# SCH_blaster_2025-10-02.net
KiCad netlist of a schematic drawn in EasyEDA
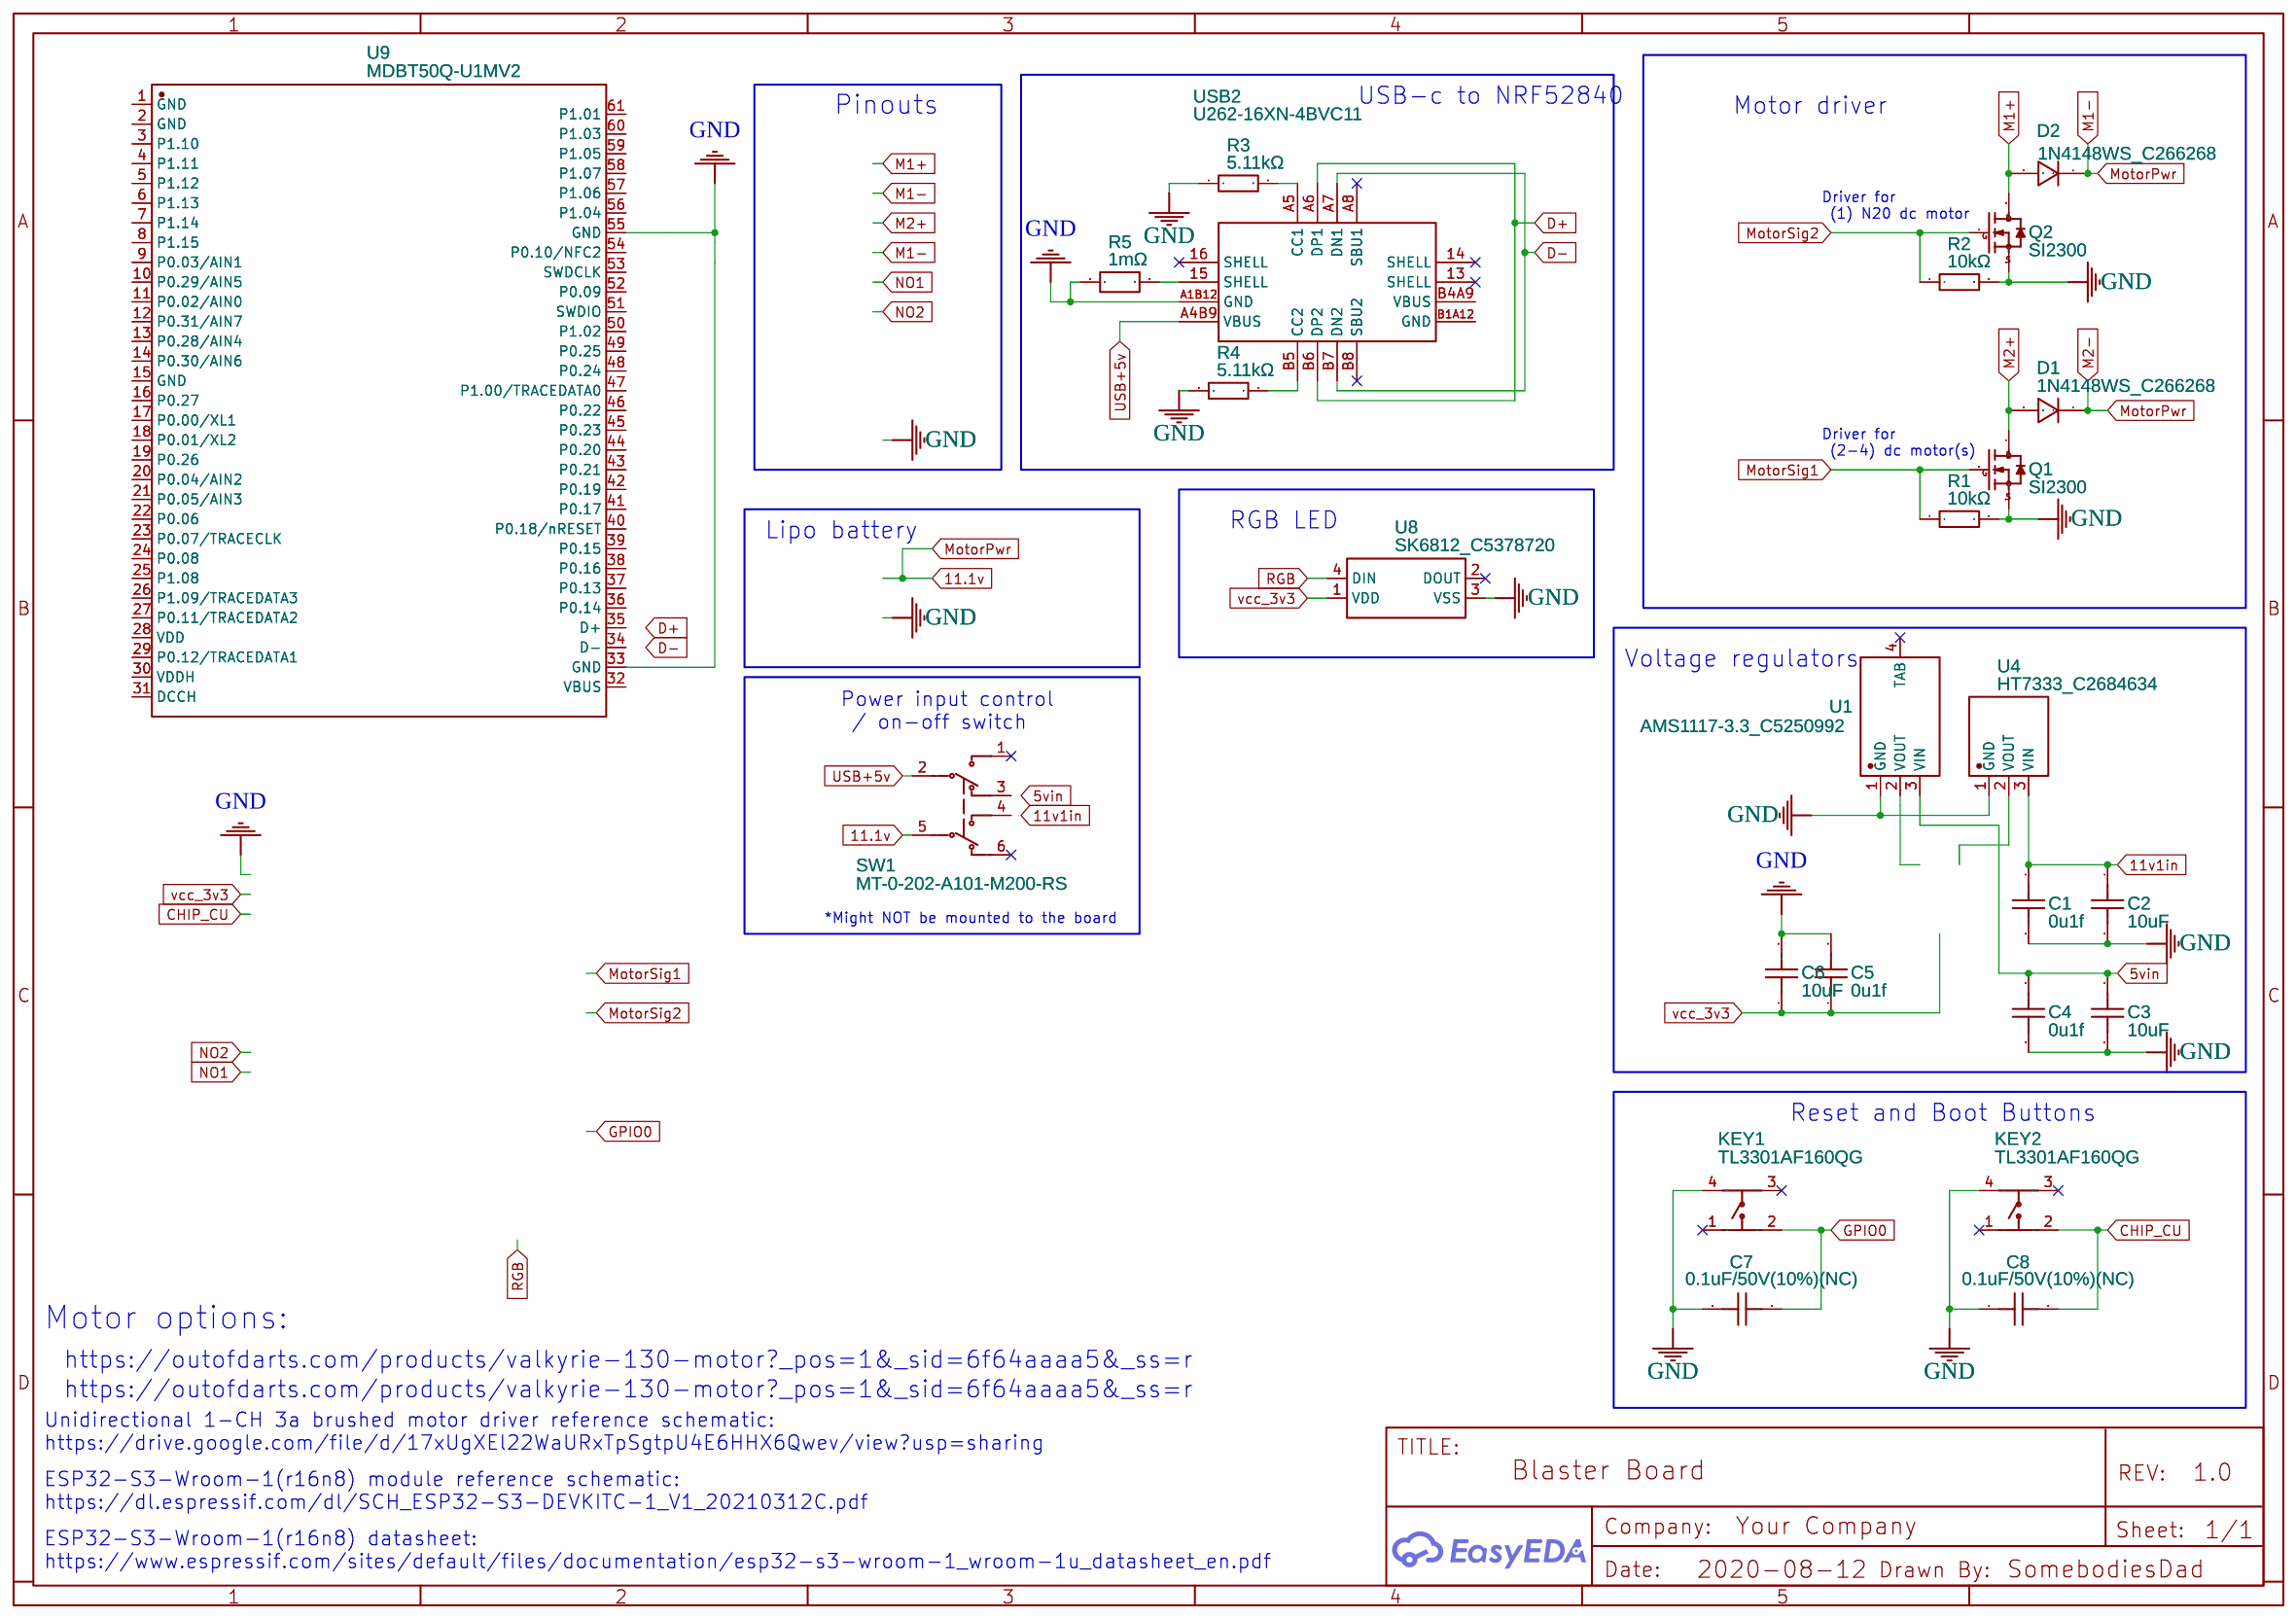
[diagram p0: Blaster Board]
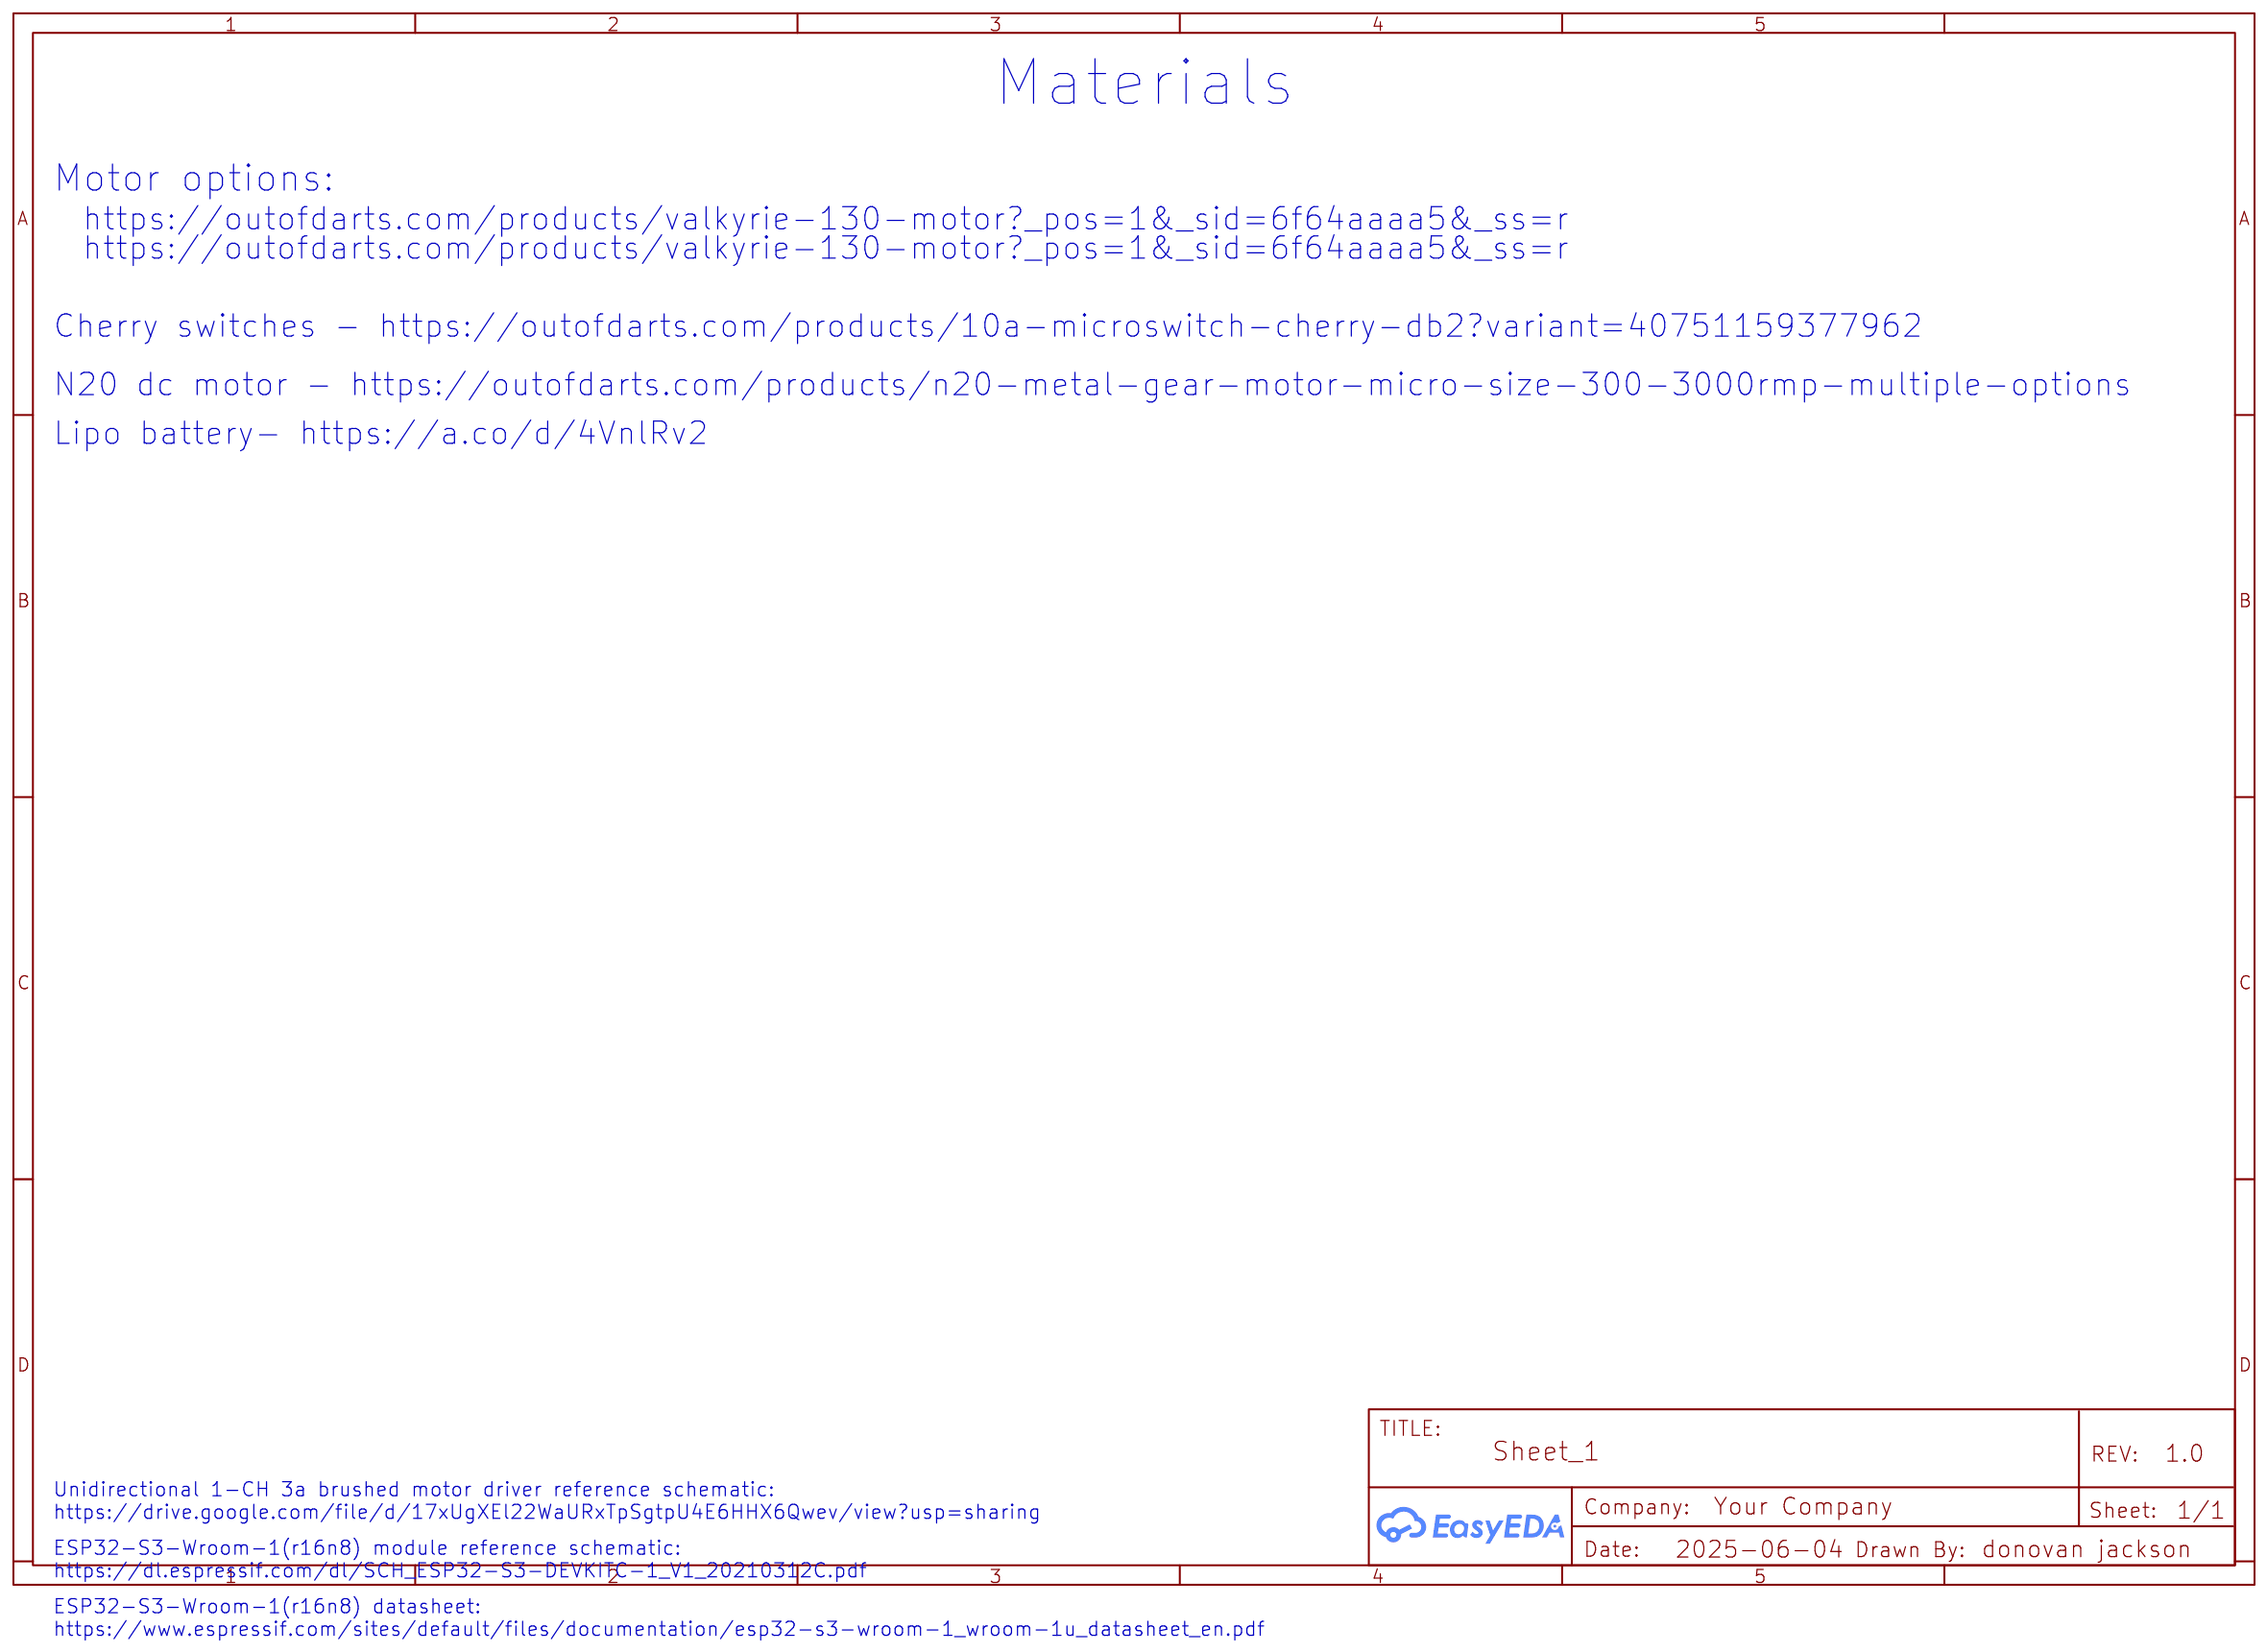
[diagram p1: Materials]

(export (version "E")
  (design (tool "Eeschema 10.0.6"))
  (components
    (comp (ref "C1") (value "0u1f") (libsource (lib "") (part "C_0603_US")))
    (comp (ref "C2") (value "10uF") (libsource (lib "") (part "C_0603_US")))
    (comp (ref "C3") (value "10uF") (libsource (lib "") (part "C_0603_US")))
    (comp (ref "C4") (value "0u1f") (libsource (lib "") (part "C_0603_US")))
    (comp (ref "C5") (value "0u1f") (libsource (lib "") (part "C_0603_US_1")))
    (comp (ref "C6") (value "10uF") (libsource (lib "") (part "C_0603_US_1")))
    (comp (ref "C7") (value "0.1uF/50V(10%)(NC)") (libsource (lib "") (part "C_0603_US_2")))
    (comp (ref "C8") (value "0.1uF/50V(10%)(NC)") (libsource (lib "") (part "C_0603_US_2")))
    (comp (ref "D1")
      (value "1N4148WS_C266268")
      (fields (field (name "Manufacturer Part") "1N4148WS") (field (name "Manufacturer") "GOOD-ARK(固锝)"))
      (libsource (lib "") (part "1N4148WS_C266268"))
    )
    (comp (ref "D2")
      (value "1N4148WS_C266268")
      (fields (field (name "Manufacturer Part") "1N4148WS") (field (name "Manufacturer") "GOOD-ARK(固锝)"))
      (libsource (lib "") (part "1N4148WS_C266268"))
    )
    (comp (ref "KEY1")
      (value "TL3301AF160QG")
      (fields (field (name "Manufacturer") "E-Switch"))
      (libsource (lib "") (part "TL3301AF160QG"))
    )
    (comp (ref "KEY2")
      (value "TL3301AF160QG")
      (fields (field (name "Manufacturer") "E-Switch"))
      (libsource (lib "") (part "TL3301AF160QG"))
    )
    (comp (ref "Q1")
      (value "SI2300")
      (fields (field (name "Manufacturer") "Hottech(合科泰)"))
      (libsource (lib "") (part "SI2300"))
    )
    (comp (ref "Q2")
      (value "SI2300")
      (fields (field (name "Manufacturer") "Hottech(合科泰)"))
      (libsource (lib "") (part "SI2300"))
    )
    (comp (ref "R1")
      (value "10kΩ")
      (fields
        (field (name "Manufacturer Part") "0805W8F1002T5E")
        (field (name "Manufacturer") "UNI-ROYAL(厚声)")
      )
      (libsource (lib "") (part "0805W8F1002T5E"))
    )
    (comp (ref "R2")
      (value "10kΩ")
      (fields
        (field (name "Manufacturer Part") "0805W8F1002T5E")
        (field (name "Manufacturer") "UNI-ROYAL(厚声)")
      )
      (libsource (lib "") (part "0805W8F1002T5E"))
    )
    (comp (ref "R3")
      (value "5.11kΩ")
      (fields
        (field (name "Manufacturer Part") "0201WMF5111TEE")
        (field (name "Manufacturer") "UNI-ROYAL(厚声)")
      )
      (libsource (lib "") (part "0201WMF5111TEE"))
    )
    (comp (ref "R4")
      (value "5.11kΩ")
      (fields
        (field (name "Manufacturer Part") "0201WMF5111TEE")
        (field (name "Manufacturer") "UNI-ROYAL(厚声)")
      )
      (libsource (lib "") (part "0201WMF5111TEE"))
    )
    (comp (ref "R5")
      (value "1mΩ")
      (fields
        (field (name "Manufacturer Part") "WFC08051L000FE66")
        (field (name "Manufacturer") "VISHAY(威世)")
      )
      (libsource (lib "") (part "WFC08051L000FE66"))
    )
    (comp (ref "SW1")
      (value "MT-0-202-A101-M200-RS")
      (fields (field (name "Manufacturer") "YUEN FUNG(源丰)"))
      (libsource (lib "") (part "MT-0-202-A101-M200-RS"))
    )
    (comp (ref "U1")
      (value "AMS1117-3.3_C5250992")
      (fields (field (name "Manufacturer Part") "AMS1117-3.3") (field (name "Manufacturer") "TWGMC(台湾迪嘉)"))
      (libsource (lib "") (part "AMS1117-3.3_C5250992"))
    )
    (comp (ref "U4")
      (value "HT7333_C2684634")
      (fields (field (name "Manufacturer Part") "HT7333") (field (name "Manufacturer") "国芯佳品"))
      (libsource (lib "") (part "HT7333_C2684634"))
    )
    (comp (ref "U8")
      (value "SK6812_C5378720")
      (fields (field (name "Manufacturer Part") "SK6812") (field (name "Manufacturer") "欧思科光电"))
      (libsource (lib "") (part "SK6812_C5378720"))
    )
    (comp (ref "U9")
      (value "MDBT50Q-U1MV2")
      (fields (field (name "Manufacturer") "RAYTAC"))
      (libsource (lib "") (part "MDBT50Q-U1MV2"))
    )
    (comp (ref "USB2")
      (value "U262-16XN-4BVC11")
      (fields
        (field (name "Manufacturer Part") "U262-161N-4BVC11")
        (field (name "Manufacturer") "XKB Connection(中国星坤)")
      )
      (libsource (lib "") (part "U262-16XN-4BVC11"))
    )
  )
  (nets
    (net (code "1") (name "5vin") (class "Default")
      (node (ref "C3") (pin "1") (pinfunction "1_1") (pintype "unspecified"))
      (node (ref "C4") (pin "1") (pinfunction "1_1") (pintype "unspecified"))
      (node (ref "U1") (pin "3") (pinfunction "VIN_3") (pintype "unspecified"))
    )
    (net (code "2") (name "11.1v") (class "Default")
      (node (ref "D1") (pin "1") (pinfunction "1_1") (pintype "unspecified"))
      (node (ref "D2") (pin "1") (pinfunction "1_1") (pintype "unspecified"))
      (node (ref "SW1") (pin "5") (pinfunction "5_5") (pintype "unspecified"))
    )
    (net (code "3") (name "11v1in") (class "Default")
      (node (ref "C1") (pin "1") (pinfunction "1_1") (pintype "unspecified"))
      (node (ref "C2") (pin "1") (pinfunction "1_1") (pintype "unspecified"))
      (node (ref "U4") (pin "3") (pinfunction "VIN_3") (pintype "unspecified"))
    )
    (net (code "4") (name "CHIP_CU") (class "Default")
      (node (ref "C8") (pin "2") (pinfunction "2_2") (pintype "unspecified"))
      (node (ref "KEY2") (pin "2") (pinfunction "2_2") (pintype "unspecified"))
    )
    (net (code "5") (name "D+") (class "Default")
      (node (ref "USB2") (pin "A6") (pinfunction "DP1_A6") (pintype "unspecified"))
      (node (ref "USB2") (pin "B6") (pinfunction "DP2_B6") (pintype "unspecified"))
    )
    (net (code "6") (name "D-") (class "Default")
      (node (ref "USB2") (pin "A7") (pinfunction "DN1_A7") (pintype "unspecified"))
      (node (ref "USB2") (pin "B7") (pinfunction "DN2_B7") (pintype "unspecified"))
    )
    (net (code "7") (name "GND") (class "Default")
      (node (ref "C1") (pin "2") (pinfunction "2_2") (pintype "unspecified"))
      (node (ref "C2") (pin "2") (pinfunction "2_2") (pintype "unspecified"))
      (node (ref "C3") (pin "2") (pinfunction "2_2") (pintype "unspecified"))
      (node (ref "C4") (pin "2") (pinfunction "2_2") (pintype "unspecified"))
      (node (ref "C5") (pin "2") (pinfunction "2_2") (pintype "unspecified"))
      (node (ref "C6") (pin "2") (pinfunction "2_2") (pintype "unspecified"))
      (node (ref "C7") (pin "1") (pinfunction "1_1") (pintype "unspecified"))
      (node (ref "C8") (pin "1") (pinfunction "1_1") (pintype "unspecified"))
      (node (ref "KEY1") (pin "4") (pinfunction "4_4") (pintype "unspecified"))
      (node (ref "KEY2") (pin "4") (pinfunction "4_4") (pintype "unspecified"))
      (node (ref "Q1") (pin "2") (pinfunction "S_2") (pintype "unspecified"))
      (node (ref "Q2") (pin "2") (pinfunction "S_2") (pintype "unspecified"))
      (node (ref "R1") (pin "2") (pinfunction "2_2") (pintype "input"))
      (node (ref "R2") (pin "2") (pinfunction "2_2") (pintype "input"))
      (node (ref "R3") (pin "1") (pinfunction "1_1") (pintype "unspecified"))
      (node (ref "R4") (pin "1") (pinfunction "1_1") (pintype "unspecified"))
      (node (ref "R5") (pin "1") (pinfunction "1_1") (pintype "unspecified"))
      (node (ref "U1") (pin "1") (pinfunction "GND_1") (pintype "unspecified"))
      (node (ref "U4") (pin "1") (pinfunction "GND_1") (pintype "unspecified"))
      (node (ref "U8") (pin "3") (pinfunction "VSS_3") (pintype "unspecified"))
      (node (ref "U9") (pin "33") (pinfunction "GND_33") (pintype "unspecified"))
      (node (ref "U9") (pin "55") (pinfunction "GND_55") (pintype "unspecified"))
      (node (ref "USB2") (pin "A1B12") (pinfunction "GND_A1B12") (pintype "unspecified"))
    )
    (net (code "8") (name "GPIO0") (class "Default")
      (node (ref "C7") (pin "2") (pinfunction "2_2") (pintype "unspecified"))
      (node (ref "KEY1") (pin "2") (pinfunction "2_2") (pintype "unspecified"))
    )
    (net (code "9") (name "M1+") (class "Default")
      (node (ref "D2") (pin "2") (pinfunction "2_2") (pintype "unspecified"))
      (node (ref "Q2") (pin "3") (pinfunction "D_3") (pintype "unspecified"))
    )
    (net (code "10") (name "M2+") (class "Default")
      (node (ref "D1") (pin "2") (pinfunction "2_2") (pintype "unspecified"))
      (node (ref "Q1") (pin "3") (pinfunction "D_3") (pintype "unspecified"))
    )
    (net (code "11") (name "MotorSig1") (class "Default")
      (node (ref "Q1") (pin "1") (pinfunction "G_1") (pintype "unspecified"))
      (node (ref "R1") (pin "1") (pinfunction "1_1") (pintype "input"))
    )
    (net (code "12") (name "MotorSig2") (class "Default")
      (node (ref "Q2") (pin "1") (pinfunction "G_1") (pintype "unspecified"))
      (node (ref "R2") (pin "1") (pinfunction "1_1") (pintype "input"))
    )
    (net (code "15") (name "Net-(R5-Pad2)") (class "Default")
      (node (ref "R5") (pin "2") (pinfunction "2_2") (pintype "unspecified"))
      (node (ref "USB2") (pin "15") (pinfunction "SHELL_15") (pintype "unspecified"))
    )
    (net (code "16") (name "Net-(USB2-CC1)") (class "Default")
      (node (ref "R3") (pin "2") (pinfunction "2_2") (pintype "unspecified"))
      (node (ref "USB2") (pin "A5") (pinfunction "CC1_A5") (pintype "unspecified"))
    )
    (net (code "17") (name "Net-(USB2-CC2)") (class "Default")
      (node (ref "R4") (pin "2") (pinfunction "2_2") (pintype "unspecified"))
      (node (ref "USB2") (pin "B5") (pinfunction "CC2_B5") (pintype "unspecified"))
    )
    (net (code "18") (name "RGB") (class "Default")
      (node (ref "U8") (pin "4") (pinfunction "DIN_4") (pintype "unspecified"))
    )
    (net (code "19") (name "USB+5v") (class "Default")
      (node (ref "SW1") (pin "2") (pinfunction "2_2") (pintype "unspecified"))
      (node (ref "USB2") (pin "A4B9") (pinfunction "VBUS_A4B9") (pintype "unspecified"))
    )
    (net (code "20") (name "unconnected-(KEY1-Pad1)") (class "Default")
      (node (ref "KEY1") (pin "1") (pinfunction "1_1") (pintype "unspecified+no_connect"))
    )
    (net (code "21") (name "unconnected-(KEY1-Pad3)") (class "Default")
      (node (ref "KEY1") (pin "3") (pinfunction "3_3") (pintype "unspecified+no_connect"))
    )
    (net (code "22") (name "unconnected-(KEY2-Pad1)") (class "Default")
      (node (ref "KEY2") (pin "1") (pinfunction "1_1") (pintype "unspecified+no_connect"))
    )
    (net (code "23") (name "unconnected-(KEY2-Pad3)") (class "Default")
      (node (ref "KEY2") (pin "3") (pinfunction "3_3") (pintype "unspecified+no_connect"))
    )
    (net (code "24") (name "unconnected-(SW1-Pad1)") (class "Default")
      (node (ref "SW1") (pin "1") (pinfunction "1_1") (pintype "unspecified+no_connect"))
    )
    (net (code "25") (name "unconnected-(SW1-Pad3)") (class "Default")
      (node (ref "SW1") (pin "3") (pinfunction "3_3") (pintype "unspecified"))
    )
    (net (code "26") (name "unconnected-(SW1-Pad4)") (class "Default")
      (node (ref "SW1") (pin "4") (pinfunction "4_4") (pintype "unspecified"))
    )
    (net (code "27") (name "unconnected-(SW1-Pad6)") (class "Default")
      (node (ref "SW1") (pin "6") (pinfunction "6_6") (pintype "unspecified+no_connect"))
    )
    (net (code "28") (name "unconnected-(U1-TAB-Pad4)") (class "Default")
      (node (ref "U1") (pin "4") (pinfunction "TAB_4") (pintype "unspecified+no_connect"))
    )
    (net (code "29") (name "unconnected-(U1-VOUT-Pad2)") (class "Default")
      (node (ref "U1") (pin "2") (pinfunction "VOUT_2") (pintype "unspecified"))
    )
    (net (code "30") (name "unconnected-(U4-VOUT-Pad2)") (class "Default")
      (node (ref "U4") (pin "2") (pinfunction "VOUT_2") (pintype "unspecified"))
    )
    (net (code "31") (name "unconnected-(U8-DOUT-Pad2)") (class "Default")
      (node (ref "U8") (pin "2") (pinfunction "DOUT_2") (pintype "unspecified+no_connect"))
    )
    (net (code "32") (name "unconnected-(U9-D+-Pad35)") (class "Default")
      (node (ref "U9") (pin "35") (pinfunction "D+_35") (pintype "unspecified"))
    )
    (net (code "33") (name "unconnected-(U9-D--Pad34)") (class "Default")
      (node (ref "U9") (pin "34") (pinfunction "D-_34") (pintype "unspecified"))
    )
    (net (code "34") (name "unconnected-(U9-DCCH-Pad31)") (class "Default")
      (node (ref "U9") (pin "31") (pinfunction "DCCH_31") (pintype "unspecified"))
    )
    (net (code "35") (name "unconnected-(U9-GND-Pad1)") (class "Default")
      (node (ref "U9") (pin "1") (pinfunction "GND_1") (pintype "unspecified"))
    )
    (net (code "36") (name "unconnected-(U9-GND-Pad2)") (class "Default")
      (node (ref "U9") (pin "2") (pinfunction "GND_2") (pintype "unspecified"))
    )
    (net (code "37") (name "unconnected-(U9-GND-Pad15)") (class "Default")
      (node (ref "U9") (pin "15") (pinfunction "GND_15") (pintype "unspecified"))
    )
    (net (code "38") (name "unconnected-(U9-P0.00{slash}XL1-Pad17)") (class "Default")
      (node (ref "U9") (pin "17") (pinfunction "P0.00/XL1_17") (pintype "unspecified"))
    )
    (net (code "39") (name "unconnected-(U9-P0.01{slash}XL2-Pad18)") (class "Default")
      (node (ref "U9") (pin "18") (pinfunction "P0.01/XL2_18") (pintype "unspecified"))
    )
    (net (code "40") (name "unconnected-(U9-P0.02{slash}AIN0-Pad11)") (class "Default")
      (node (ref "U9") (pin "11") (pinfunction "P0.02/AIN0_11") (pintype "unspecified"))
    )
    (net (code "41") (name "unconnected-(U9-P0.03{slash}AIN1-Pad9)") (class "Default")
      (node (ref "U9") (pin "9") (pinfunction "P0.03/AIN1_9") (pintype "unspecified"))
    )
    (net (code "42") (name "unconnected-(U9-P0.04{slash}AIN2-Pad20)") (class "Default")
      (node (ref "U9") (pin "20") (pinfunction "P0.04/AIN2_20") (pintype "unspecified"))
    )
    (net (code "43") (name "unconnected-(U9-P0.05{slash}AIN3-Pad21)") (class "Default")
      (node (ref "U9") (pin "21") (pinfunction "P0.05/AIN3_21") (pintype "unspecified"))
    )
    (net (code "44") (name "unconnected-(U9-P0.06-Pad22)") (class "Default")
      (node (ref "U9") (pin "22") (pinfunction "P0.06_22") (pintype "unspecified"))
    )
    (net (code "45") (name "unconnected-(U9-P0.07{slash}TRACECLK-Pad23)") (class "Default")
      (node (ref "U9") (pin "23") (pinfunction "P0.07/TRACECLK_23") (pintype "unspecified"))
    )
    (net (code "46") (name "unconnected-(U9-P0.08-Pad24)") (class "Default")
      (node (ref "U9") (pin "24") (pinfunction "P0.08_24") (pintype "unspecified"))
    )
    (net (code "47") (name "unconnected-(U9-P0.09-Pad52)") (class "Default")
      (node (ref "U9") (pin "52") (pinfunction "P0.09_52") (pintype "unspecified"))
    )
    (net (code "48") (name "unconnected-(U9-P0.10{slash}NFC2-Pad54)") (class "Default")
      (node (ref "U9") (pin "54") (pinfunction "P0.10/NFC2_54") (pintype "unspecified"))
    )
    (net (code "49") (name "unconnected-(U9-P0.11{slash}TRACEDATA2-Pad27)") (class "Default")
      (node (ref "U9") (pin "27") (pinfunction "P0.11/TRACEDATA2_27") (pintype "unspecified"))
    )
    (net (code "50") (name "unconnected-(U9-P0.12{slash}TRACEDATA1-Pad29)") (class "Default")
      (node (ref "U9") (pin "29") (pinfunction "P0.12/TRACEDATA1_29") (pintype "unspecified"))
    )
    (net (code "51") (name "unconnected-(U9-P0.13-Pad37)") (class "Default")
      (node (ref "U9") (pin "37") (pinfunction "P0.13_37") (pintype "unspecified"))
    )
    (net (code "52") (name "unconnected-(U9-P0.14-Pad36)") (class "Default")
      (node (ref "U9") (pin "36") (pinfunction "P0.14_36") (pintype "unspecified"))
    )
    (net (code "53") (name "unconnected-(U9-P0.15-Pad39)") (class "Default")
      (node (ref "U9") (pin "39") (pinfunction "P0.15_39") (pintype "unspecified"))
    )
    (net (code "54") (name "unconnected-(U9-P0.16-Pad38)") (class "Default")
      (node (ref "U9") (pin "38") (pinfunction "P0.16_38") (pintype "unspecified"))
    )
    (net (code "55") (name "unconnected-(U9-P0.17-Pad41)") (class "Default")
      (node (ref "U9") (pin "41") (pinfunction "P0.17_41") (pintype "unspecified"))
    )
    (net (code "56") (name "unconnected-(U9-P0.18{slash}nRESET-Pad40)") (class "Default")
      (node (ref "U9") (pin "40") (pinfunction "P0.18/nRESET_40") (pintype "unspecified"))
    )
    (net (code "57") (name "unconnected-(U9-P0.19-Pad42)") (class "Default")
      (node (ref "U9") (pin "42") (pinfunction "P0.19_42") (pintype "unspecified"))
    )
    (net (code "58") (name "unconnected-(U9-P0.20-Pad44)") (class "Default")
      (node (ref "U9") (pin "44") (pinfunction "P0.20_44") (pintype "unspecified"))
    )
    (net (code "59") (name "unconnected-(U9-P0.21-Pad43)") (class "Default")
      (node (ref "U9") (pin "43") (pinfunction "P0.21_43") (pintype "unspecified"))
    )
    (net (code "60") (name "unconnected-(U9-P0.22-Pad46)") (class "Default")
      (node (ref "U9") (pin "46") (pinfunction "P0.22_46") (pintype "unspecified"))
    )
    (net (code "61") (name "unconnected-(U9-P0.23-Pad45)") (class "Default")
      (node (ref "U9") (pin "45") (pinfunction "P0.23_45") (pintype "unspecified"))
    )
    (net (code "62") (name "unconnected-(U9-P0.24-Pad48)") (class "Default")
      (node (ref "U9") (pin "48") (pinfunction "P0.24_48") (pintype "unspecified"))
    )
    (net (code "63") (name "unconnected-(U9-P0.25-Pad49)") (class "Default")
      (node (ref "U9") (pin "49") (pinfunction "P0.25_49") (pintype "unspecified"))
    )
    (net (code "64") (name "unconnected-(U9-P0.26-Pad19)") (class "Default")
      (node (ref "U9") (pin "19") (pinfunction "P0.26_19") (pintype "unspecified"))
    )
    (net (code "65") (name "unconnected-(U9-P0.27-Pad16)") (class "Default")
      (node (ref "U9") (pin "16") (pinfunction "P0.27_16") (pintype "unspecified"))
    )
    (net (code "66") (name "unconnected-(U9-P0.28{slash}AIN4-Pad13)") (class "Default")
      (node (ref "U9") (pin "13") (pinfunction "P0.28/AIN4_13") (pintype "unspecified"))
    )
    (net (code "67") (name "unconnected-(U9-P0.29{slash}AIN5-Pad10)") (class "Default")
      (node (ref "U9") (pin "10") (pinfunction "P0.29/AIN5_10") (pintype "unspecified"))
    )
    (net (code "68") (name "unconnected-(U9-P0.30{slash}AIN6-Pad14)") (class "Default")
      (node (ref "U9") (pin "14") (pinfunction "P0.30/AIN6_14") (pintype "unspecified"))
    )
    (net (code "69") (name "unconnected-(U9-P0.31{slash}AIN7-Pad12)") (class "Default")
      (node (ref "U9") (pin "12") (pinfunction "P0.31/AIN7_12") (pintype "unspecified"))
    )
    (net (code "70") (name "unconnected-(U9-P1.00{slash}TRACEDATA0-Pad47)") (class "Default")
      (node (ref "U9") (pin "47") (pinfunction "P1.00/TRACEDATA0_47") (pintype "unspecified"))
    )
    (net (code "71") (name "unconnected-(U9-P1.01-Pad61)") (class "Default")
      (node (ref "U9") (pin "61") (pinfunction "P1.01_61") (pintype "unspecified"))
    )
    (net (code "72") (name "unconnected-(U9-P1.02-Pad50)") (class "Default")
      (node (ref "U9") (pin "50") (pinfunction "P1.02_50") (pintype "unspecified"))
    )
    (net (code "73") (name "unconnected-(U9-P1.03-Pad60)") (class "Default")
      (node (ref "U9") (pin "60") (pinfunction "P1.03_60") (pintype "unspecified"))
    )
    (net (code "74") (name "unconnected-(U9-P1.04-Pad56)") (class "Default")
      (node (ref "U9") (pin "56") (pinfunction "P1.04_56") (pintype "unspecified"))
    )
    (net (code "75") (name "unconnected-(U9-P1.05-Pad59)") (class "Default")
      (node (ref "U9") (pin "59") (pinfunction "P1.05_59") (pintype "unspecified"))
    )
    (net (code "76") (name "unconnected-(U9-P1.06-Pad57)") (class "Default")
      (node (ref "U9") (pin "57") (pinfunction "P1.06_57") (pintype "unspecified"))
    )
    (net (code "77") (name "unconnected-(U9-P1.07-Pad58)") (class "Default")
      (node (ref "U9") (pin "58") (pinfunction "P1.07_58") (pintype "unspecified"))
    )
    (net (code "78") (name "unconnected-(U9-P1.08-Pad25)") (class "Default")
      (node (ref "U9") (pin "25") (pinfunction "P1.08_25") (pintype "unspecified"))
    )
    (net (code "79") (name "unconnected-(U9-P1.09{slash}TRACEDATA3-Pad26)") (class "Default")
      (node (ref "U9") (pin "26") (pinfunction "P1.09/TRACEDATA3_26") (pintype "unspecified"))
    )
    (net (code "80") (name "unconnected-(U9-P1.10-Pad3)") (class "Default")
      (node (ref "U9") (pin "3") (pinfunction "P1.10_3") (pintype "unspecified"))
    )
    (net (code "81") (name "unconnected-(U9-P1.11-Pad4)") (class "Default")
      (node (ref "U9") (pin "4") (pinfunction "P1.11_4") (pintype "unspecified"))
    )
    (net (code "82") (name "unconnected-(U9-P1.12-Pad5)") (class "Default")
      (node (ref "U9") (pin "5") (pinfunction "P1.12_5") (pintype "unspecified"))
    )
    (net (code "83") (name "unconnected-(U9-P1.13-Pad6)") (class "Default")
      (node (ref "U9") (pin "6") (pinfunction "P1.13_6") (pintype "unspecified"))
    )
    (net (code "84") (name "unconnected-(U9-P1.14-Pad7)") (class "Default")
      (node (ref "U9") (pin "7") (pinfunction "P1.14_7") (pintype "unspecified"))
    )
    (net (code "85") (name "unconnected-(U9-P1.15-Pad8)") (class "Default")
      (node (ref "U9") (pin "8") (pinfunction "P1.15_8") (pintype "unspecified"))
    )
    (net (code "86") (name "unconnected-(U9-SWDCLK-Pad53)") (class "Default")
      (node (ref "U9") (pin "53") (pinfunction "SWDCLK_53") (pintype "unspecified"))
    )
    (net (code "87") (name "unconnected-(U9-SWDIO-Pad51)") (class "Default")
      (node (ref "U9") (pin "51") (pinfunction "SWDIO_51") (pintype "unspecified"))
    )
    (net (code "88") (name "unconnected-(U9-VBUS-Pad32)") (class "Default")
      (node (ref "U9") (pin "32") (pinfunction "VBUS_32") (pintype "unspecified"))
    )
    (net (code "89") (name "unconnected-(U9-VDD-Pad28)") (class "Default")
      (node (ref "U9") (pin "28") (pinfunction "VDD_28") (pintype "unspecified"))
    )
    (net (code "90") (name "unconnected-(U9-VDDH-Pad30)") (class "Default")
      (node (ref "U9") (pin "30") (pinfunction "VDDH_30") (pintype "unspecified"))
    )
    (net (code "91") (name "unconnected-(USB2-GND-PadB1A12)") (class "Default")
      (node (ref "USB2") (pin "B1A12") (pinfunction "GND_B1A12") (pintype "unspecified"))
    )
    (net (code "92") (name "unconnected-(USB2-SBU1-PadA8)") (class "Default")
      (node (ref "USB2") (pin "A8") (pinfunction "SBU1_A8") (pintype "unspecified+no_connect"))
    )
    (net (code "93") (name "unconnected-(USB2-SBU2-PadB8)") (class "Default")
      (node (ref "USB2") (pin "B8") (pinfunction "SBU2_B8") (pintype "unspecified+no_connect"))
    )
    (net (code "94") (name "unconnected-(USB2-SHELL-Pad13)") (class "Default")
      (node (ref "USB2") (pin "13") (pinfunction "SHELL_13") (pintype "unspecified+no_connect"))
    )
    (net (code "95") (name "unconnected-(USB2-SHELL-Pad14)") (class "Default")
      (node (ref "USB2") (pin "14") (pinfunction "SHELL_14") (pintype "unspecified+no_connect"))
    )
    (net (code "96") (name "unconnected-(USB2-SHELL-Pad16)") (class "Default")
      (node (ref "USB2") (pin "16") (pinfunction "SHELL_16") (pintype "unspecified+no_connect"))
    )
    (net (code "97") (name "unconnected-(USB2-VBUS-PadB4A9)") (class "Default")
      (node (ref "USB2") (pin "B4A9") (pinfunction "VBUS_B4A9") (pintype "unspecified"))
    )
    (net (code "98") (name "vcc_3v3") (class "Default")
      (node (ref "C5") (pin "1") (pinfunction "1_1") (pintype "unspecified"))
      (node (ref "C6") (pin "1") (pinfunction "1_1") (pintype "unspecified"))
      (node (ref "U8") (pin "1") (pinfunction "VDD_1") (pintype "unspecified"))
    )
  )
)
